# AUGIS_Switch_Board.net
KiCad netlist of a schematic drawn in EasyEDA
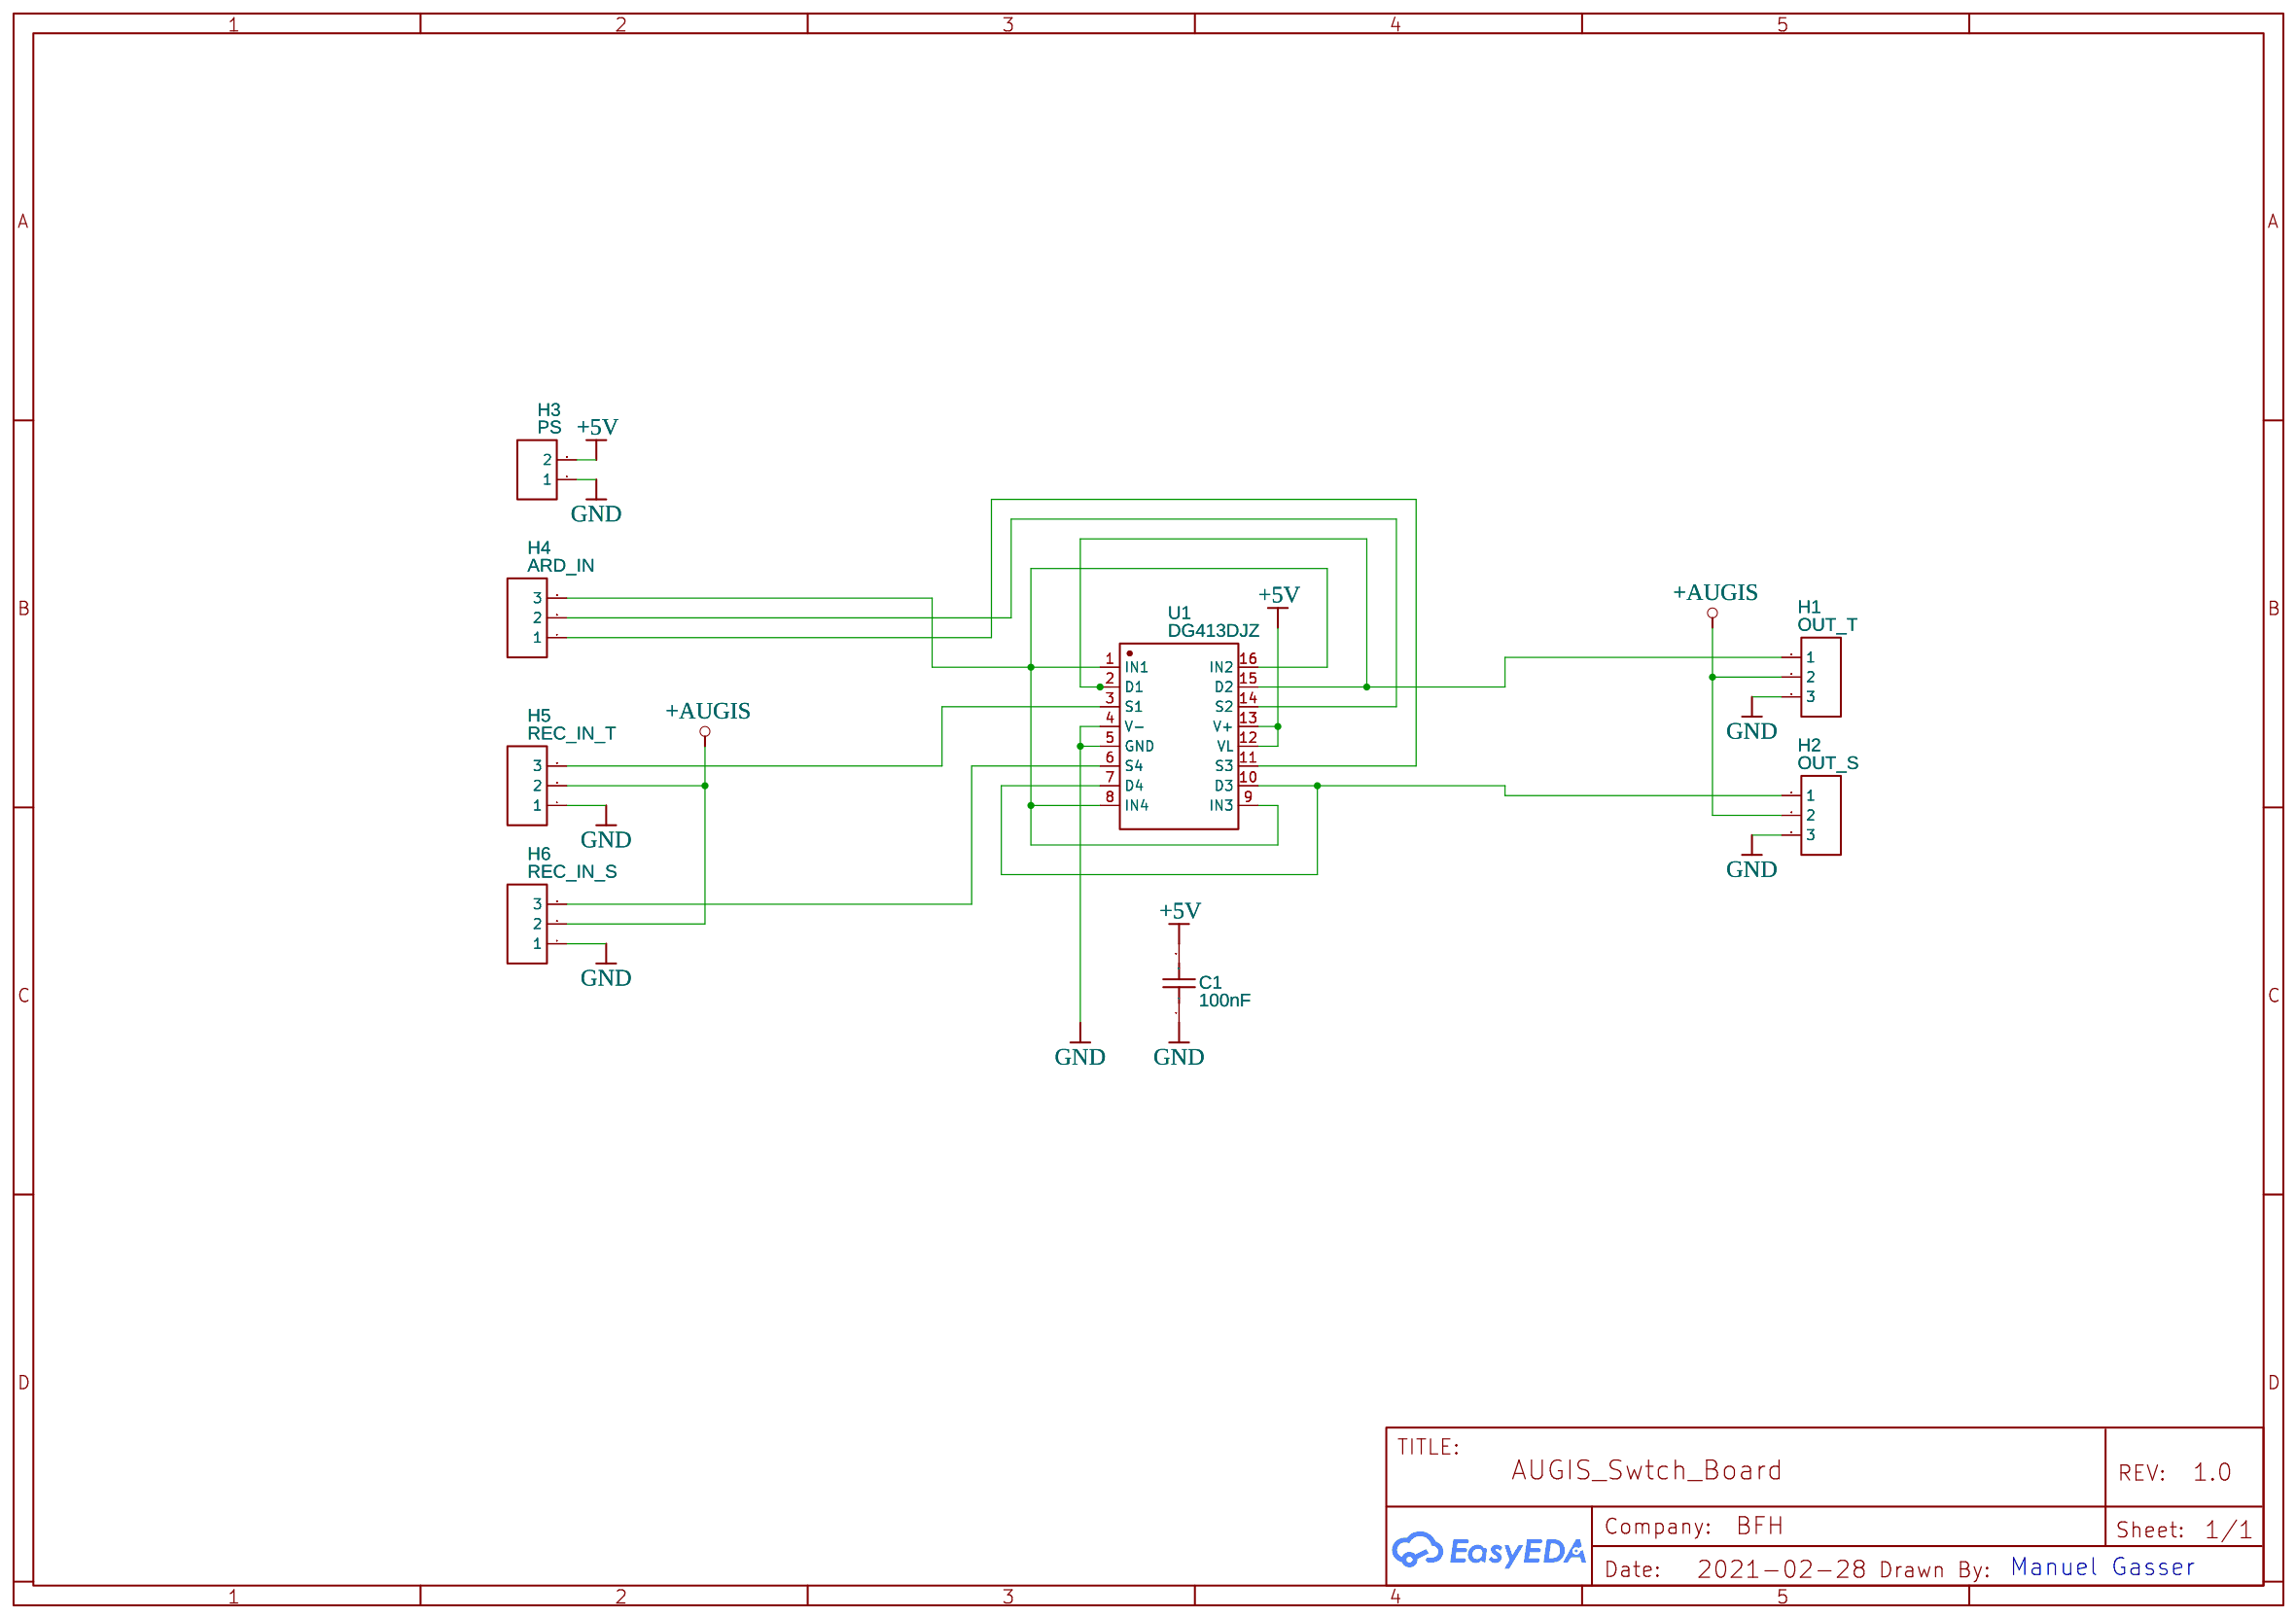
[diagram p0: schematic sheet]

(export (version "E")
  (design (tool "Eeschema 10.0.6"))
  (components
    (comp (ref "C1") (value "100nF") (libsource (lib "") (part "C_0603_US")))
    (comp (ref "H1")
      (value "OUT_T")
      (fields (field (name "BOM_Supplier Part") "C146690"))
      (libsource (lib "") (part "HDR-F-2.54_1x3_1"))
    )
    (comp (ref "H2")
      (value "OUT_S")
      (fields (field (name "BOM_Supplier Part") "C146690"))
      (libsource (lib "") (part "HDR-F-2.54_1x3_1"))
    )
    (comp (ref "H3")
      (value "PS")
      (fields (field (name "BOM_Supplier Part") "C49661"))
      (libsource (lib "") (part "HDR-F-2.54_1x2"))
    )
    (comp (ref "H4")
      (value "ARD_IN")
      (fields (field (name "BOM_Supplier Part") "C146690"))
      (libsource (lib "") (part "HDR-F-2.54_1x3"))
    )
    (comp (ref "H5")
      (value "REC_IN_T")
      (fields (field (name "BOM_Supplier Part") "C146690"))
      (libsource (lib "") (part "HDR-F-2.54_1x3"))
    )
    (comp (ref "H6")
      (value "REC_IN_S")
      (fields (field (name "BOM_Supplier Part") "C146690"))
      (libsource (lib "") (part "HDR-F-2.54_1x3"))
    )
    (comp (ref "U1") (value "DG413DJZ") (libsource (lib "") (part "DG413DJZ")))
  )
  (nets
    (net (code "1") (name "+5V") (class "Default")
      (node (ref "C1") (pin "2") (pinfunction "2_2") (pintype "unspecified"))
      (node (ref "H3") (pin "2") (pinfunction "2_2") (pintype "input"))
      (node (ref "U1") (pin "12") (pinfunction "VL_12") (pintype "unspecified"))
      (node (ref "U1") (pin "13") (pinfunction "V+_13") (pintype "unspecified"))
    )
    (net (code "2") (name "+AUGIS") (class "Default")
      (node (ref "H1") (pin "2") (pinfunction "2_2") (pintype "input"))
      (node (ref "H2") (pin "2") (pinfunction "2_2") (pintype "input"))
      (node (ref "H5") (pin "2") (pinfunction "2_2") (pintype "input"))
      (node (ref "H6") (pin "2") (pinfunction "2_2") (pintype "input"))
    )
    (net (code "3") (name "GND") (class "Default")
      (node (ref "C1") (pin "1") (pinfunction "1_1") (pintype "unspecified"))
      (node (ref "H1") (pin "3") (pinfunction "3_3") (pintype "input"))
      (node (ref "H2") (pin "3") (pinfunction "3_3") (pintype "input"))
      (node (ref "H3") (pin "1") (pinfunction "1_1") (pintype "input"))
      (node (ref "H5") (pin "1") (pinfunction "1_1") (pintype "input"))
      (node (ref "H6") (pin "1") (pinfunction "1_1") (pintype "input"))
      (node (ref "U1") (pin "4") (pinfunction "V-_4") (pintype "unspecified"))
      (node (ref "U1") (pin "5") (pinfunction "GND_5") (pintype "unspecified"))
    )
    (net (code "4") (name "Net-(U1-D1)") (class "Default")
      (node (ref "H1") (pin "1") (pinfunction "1_1") (pintype "input"))
      (node (ref "U1") (pin "15") (pinfunction "D2_15") (pintype "unspecified"))
      (node (ref "U1") (pin "2") (pinfunction "D1_2") (pintype "unspecified"))
    )
    (net (code "5") (name "Net-(U1-D3)") (class "Default")
      (node (ref "H2") (pin "1") (pinfunction "1_1") (pintype "input"))
      (node (ref "U1") (pin "10") (pinfunction "D3_10") (pintype "unspecified"))
      (node (ref "U1") (pin "7") (pinfunction "D4_7") (pintype "unspecified"))
    )
    (net (code "6") (name "Net-(U1-IN1)") (class "Default")
      (node (ref "H4") (pin "3") (pinfunction "3_3") (pintype "input"))
      (node (ref "U1") (pin "1") (pinfunction "IN1_1") (pintype "unspecified"))
      (node (ref "U1") (pin "16") (pinfunction "IN2_16") (pintype "unspecified"))
      (node (ref "U1") (pin "8") (pinfunction "IN4_8") (pintype "unspecified"))
      (node (ref "U1") (pin "9") (pinfunction "IN3_9") (pintype "unspecified"))
    )
    (net (code "7") (name "Net-(U1-S1)") (class "Default")
      (node (ref "H5") (pin "3") (pinfunction "3_3") (pintype "input"))
      (node (ref "U1") (pin "3") (pinfunction "S1_3") (pintype "unspecified"))
    )
    (net (code "8") (name "Net-(U1-S2)") (class "Default")
      (node (ref "H4") (pin "2") (pinfunction "2_2") (pintype "input"))
      (node (ref "U1") (pin "14") (pinfunction "S2_14") (pintype "unspecified"))
    )
    (net (code "9") (name "Net-(U1-S3)") (class "Default")
      (node (ref "H4") (pin "1") (pinfunction "1_1") (pintype "input"))
      (node (ref "U1") (pin "11") (pinfunction "S3_11") (pintype "unspecified"))
    )
    (net (code "10") (name "Net-(U1-S4)") (class "Default")
      (node (ref "H6") (pin "3") (pinfunction "3_3") (pintype "input"))
      (node (ref "U1") (pin "6") (pinfunction "S4_6") (pintype "unspecified"))
    )
  )
)
